# Photodiode.net
KiCad netlist of a schematic drawn in Altium Designer
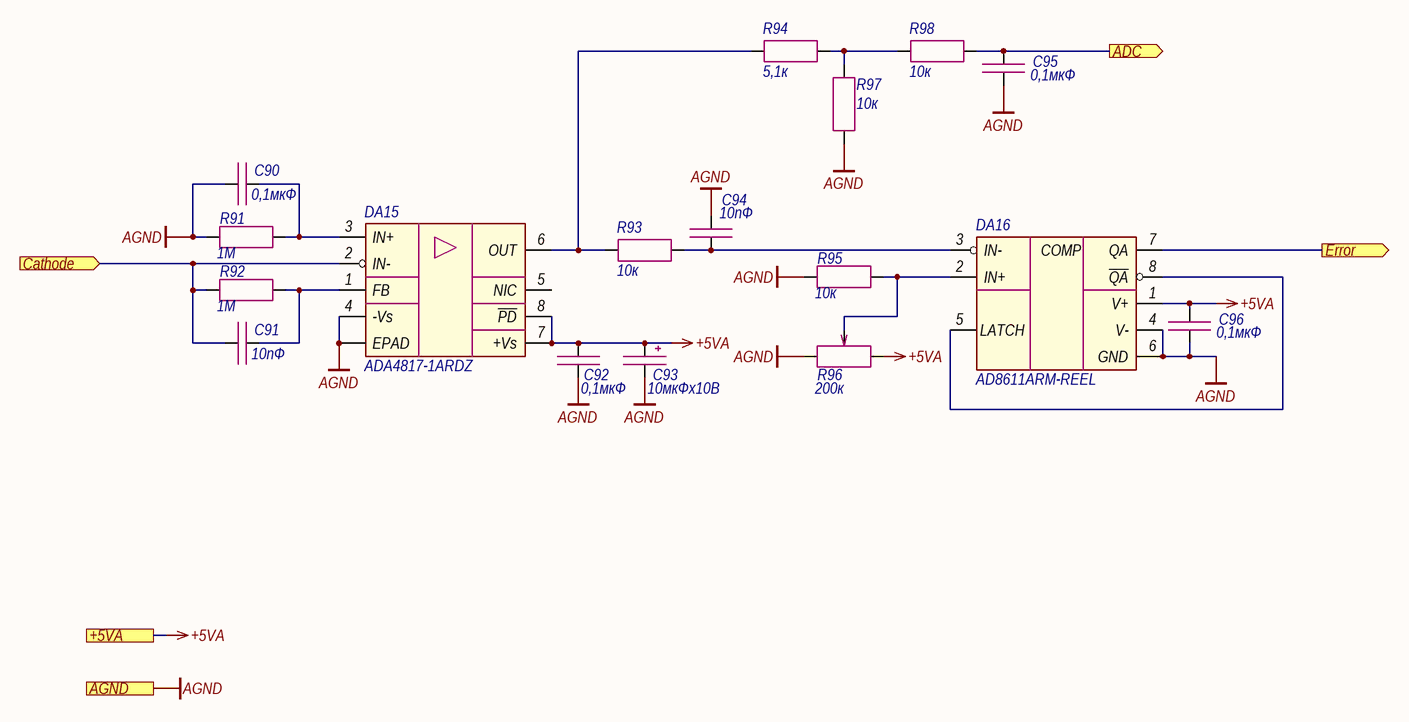
[diagram p0: Photodiode.SchDoc]

(export (version "E")
  (design (tool "Eeschema 10.0.6"))
  (components
    (comp (ref "C90")
      (value "0,1мкФ")
      (footprint "Pcb_library:CAP_0603")
      (fields (field (name "MANUFACTURER") "Murata"))
      (libsource (lib "Schem_library") (part "Capacitor"))
    )
    (comp (ref "C91")
      (value "10пФ")
      (footprint "Pcb_library:CAP_0603")
      (fields (field (name "MANUFACTURER") "Murata"))
      (libsource (lib "Schem_library") (part "Capacitor"))
    )
    (comp (ref "C92")
      (value "0,1мкФ")
      (footprint "Pcb_library:CAP_0603")
      (fields (field (name "MANUFACTURER") "Murata"))
      (libsource (lib "Schem_library") (part "Capacitor"))
    )
    (comp (ref "C93")
      (value "10мкФх10B")
      (footprint "Pcb_library:CAP_A")
      (libsource (lib "Schem_library") (part "Capacitor_Polar"))
    )
    (comp (ref "C94")
      (value "10пФ")
      (footprint "Pcb_library:CAP_0603")
      (fields (field (name "MANUFACTURER") "Murata"))
      (libsource (lib "Schem_library") (part "Capacitor"))
    )
    (comp (ref "C95")
      (value "0,1мкФ")
      (footprint "Pcb_library:CAP_0603")
      (fields (field (name "MANUFACTURER") "Murata"))
      (libsource (lib "Schem_library") (part "Capacitor"))
    )
    (comp (ref "C96")
      (value "0,1мкФ")
      (footprint "Pcb_library:CAP_0603")
      (fields (field (name "MANUFACTURER") "Murata"))
      (libsource (lib "Schem_library") (part "Capacitor"))
    )
    (comp (ref "DA15")
      (value "ADA4817-1ARDZ")
      (footprint "Pcb_library:SOIC-8 EPAD")
      (fields (field (name "MANUFACTURER") "Analog Devices"))
      (libsource (lib "Schem_library") (part "ADA4817-1ARDZ"))
    )
    (comp (ref "DA16")
      (value "AD8611ARM-REEL")
      (footprint "Pcb_library:MSOP-8")
      (fields (field (name "MANUFACTURER") "Analog Devices"))
      (libsource (lib "Schem_library") (part "AD8611"))
    )
    (comp (ref "R91")
      (value "1М")
      (footprint "Pcb_library:RES_0805")
      (fields (field (name "MANUFACTURER") "Yageo"))
      (libsource (lib "Schem_library") (part "Resistor"))
    )
    (comp (ref "R92")
      (value "1М")
      (footprint "Pcb_library:RES_0805")
      (fields (field (name "MANUFACTURER") "Yageo"))
      (libsource (lib "Schem_library") (part "Resistor"))
    )
    (comp (ref "R93")
      (value "10к")
      (footprint "Pcb_library:RES_0603")
      (fields (field (name "MANUFACTURER") "Yageo"))
      (libsource (lib "Schem_library") (part "Resistor"))
    )
    (comp (ref "R94")
      (value "5,1к")
      (footprint "Pcb_library:RES_0603")
      (fields (field (name "MANUFACTURER") "Yageo"))
      (libsource (lib "Schem_library") (part "Resistor"))
    )
    (comp (ref "R95")
      (value "10к")
      (footprint "Pcb_library:RES_0603")
      (fields (field (name "MANUFACTURER") "Yageo"))
      (libsource (lib "Schem_library") (part "Resistor"))
    )
    (comp (ref "R96")
      (value "200к")
      (footprint "Pcb_library:3224W")
      (fields (field (name "MANUFACTURER") "Bourns"))
      (libsource (lib "Schem_library") (part "Resistor_Variable"))
    )
    (comp (ref "R97")
      (value "10к")
      (footprint "Pcb_library:RES_0603")
      (fields (field (name "MANUFACTURER") "Yageo"))
      (libsource (lib "Schem_library") (part "Resistor"))
    )
    (comp (ref "R98")
      (value "10к")
      (footprint "Pcb_library:RES_0603")
      (fields (field (name "MANUFACTURER") "Yageo"))
      (libsource (lib "Schem_library") (part "Resistor"))
    )
  )
  (nets
    (net (code "1") (name "+5VA") (class "Default")
      (node (ref "C92") (pin "1") (pinfunction "1_1") (pintype "passive"))
      (node (ref "C93") (pin "1") (pinfunction "1_1") (pintype "passive"))
      (node (ref "C96") (pin "1") (pinfunction "1_1") (pintype "passive"))
      (node (ref "DA15") (pin "7") (pinfunction "+Vs_7") (pintype "passive"))
      (node (ref "DA15") (pin "8") (pinfunction "~{PD}_8") (pintype "passive"))
      (node (ref "DA16") (pin "1") (pinfunction "V+_1") (pintype "passive"))
      (node (ref "R96") (pin "3") (pintype "passive"))
    )
    (net (code "2") (name "/ADC") (class "Default")
      (node (ref "C95") (pin "1") (pinfunction "1_1") (pintype "passive"))
      (node (ref "R98") (pin "2") (pinfunction "2_2") (pintype "passive"))
    )
    (net (code "3") (name "/Cathode") (class "Default")
      (node (ref "C91") (pin "2") (pinfunction "2_2") (pintype "passive"))
      (node (ref "DA15") (pin "2") (pinfunction "IN-_2") (pintype "passive"))
      (node (ref "R92") (pin "2") (pinfunction "2_2") (pintype "passive"))
    )
    (net (code "4") (name "/Error") (class "Default")
      (node (ref "DA16") (pin "7") (pinfunction "QA_7") (pintype "passive"))
    )
    (net (code "5") (name "AGND") (class "Default")
      (node (ref "C90") (pin "1") (pinfunction "1_1") (pintype "passive"))
      (node (ref "C92") (pin "2") (pinfunction "2_2") (pintype "passive"))
      (node (ref "C93") (pin "2") (pinfunction "2_2") (pintype "passive"))
      (node (ref "C94") (pin "2") (pinfunction "2_2") (pintype "passive"))
      (node (ref "C95") (pin "2") (pinfunction "2_2") (pintype "passive"))
      (node (ref "C96") (pin "2") (pinfunction "2_2") (pintype "passive"))
      (node (ref "DA15") (pin "4") (pinfunction "-Vs_4") (pintype "passive"))
      (node (ref "DA15") (pin "EPAD") (pinfunction "EPAD_EPAD") (pintype "passive"))
      (node (ref "DA16") (pin "4") (pinfunction "V-_4") (pintype "passive"))
      (node (ref "DA16") (pin "6") (pinfunction "GND_6") (pintype "passive"))
      (node (ref "R91") (pin "2") (pinfunction "2_2") (pintype "passive"))
      (node (ref "R95") (pin "1") (pinfunction "1_1") (pintype "passive"))
      (node (ref "R96") (pin "1") (pintype "passive"))
      (node (ref "R97") (pin "2") (pinfunction "2_2") (pintype "passive"))
    )
    (net (code "6") (name "Net-(DA15-FB)") (class "Default")
      (node (ref "C91") (pin "1") (pinfunction "1_1") (pintype "passive"))
      (node (ref "DA15") (pin "1") (pinfunction "FB_1") (pintype "passive"))
      (node (ref "R92") (pin "1") (pinfunction "1_1") (pintype "passive"))
    )
    (net (code "7") (name "Net-(DA15-IN+)") (class "Default")
      (node (ref "C90") (pin "2") (pinfunction "2_2") (pintype "passive"))
      (node (ref "DA15") (pin "3") (pinfunction "IN+_3") (pintype "passive"))
      (node (ref "R91") (pin "1") (pinfunction "1_1") (pintype "passive"))
    )
    (net (code "8") (name "Net-(DA15-OUT)") (class "Default")
      (node (ref "DA15") (pin "6") (pinfunction "OUT_6") (pintype "passive"))
      (node (ref "R93") (pin "1") (pinfunction "1_1") (pintype "passive"))
      (node (ref "R94") (pin "1") (pinfunction "1_1") (pintype "passive"))
    )
    (net (code "9") (name "Net-(DA16-IN+)") (class "Default")
      (node (ref "DA16") (pin "2") (pinfunction "IN+_2") (pintype "passive"))
      (node (ref "R95") (pin "2") (pinfunction "2_2") (pintype "passive"))
      (node (ref "R96") (pin "2") (pintype "passive"))
    )
    (net (code "10") (name "Net-(DA16-IN-)") (class "Default")
      (node (ref "C94") (pin "1") (pinfunction "1_1") (pintype "passive"))
      (node (ref "DA16") (pin "3") (pinfunction "IN-_3") (pintype "passive"))
      (node (ref "R93") (pin "2") (pinfunction "2_2") (pintype "passive"))
    )
    (net (code "11") (name "Net-(DA16-LATCH)") (class "Default")
      (node (ref "DA16") (pin "5") (pinfunction "LATCH_5") (pintype "passive"))
      (node (ref "DA16") (pin "8") (pinfunction "~{QA}_8") (pintype "passive"))
    )
    (net (code "12") (name "Net-(R94-Pad2)") (class "Default")
      (node (ref "R94") (pin "2") (pinfunction "2_2") (pintype "passive"))
      (node (ref "R97") (pin "1") (pinfunction "1_1") (pintype "passive"))
      (node (ref "R98") (pin "1") (pinfunction "1_1") (pintype "passive"))
    )
    (net (code "13") (name "unconnected-(DA15-NIC-Pad5)") (class "Default")
      (node (ref "DA15") (pin "5") (pinfunction "NIC_5") (pintype "passive"))
    )
  )
)
